# FMC_Main.net
KiCad netlist of a schematic drawn in Altium Designer
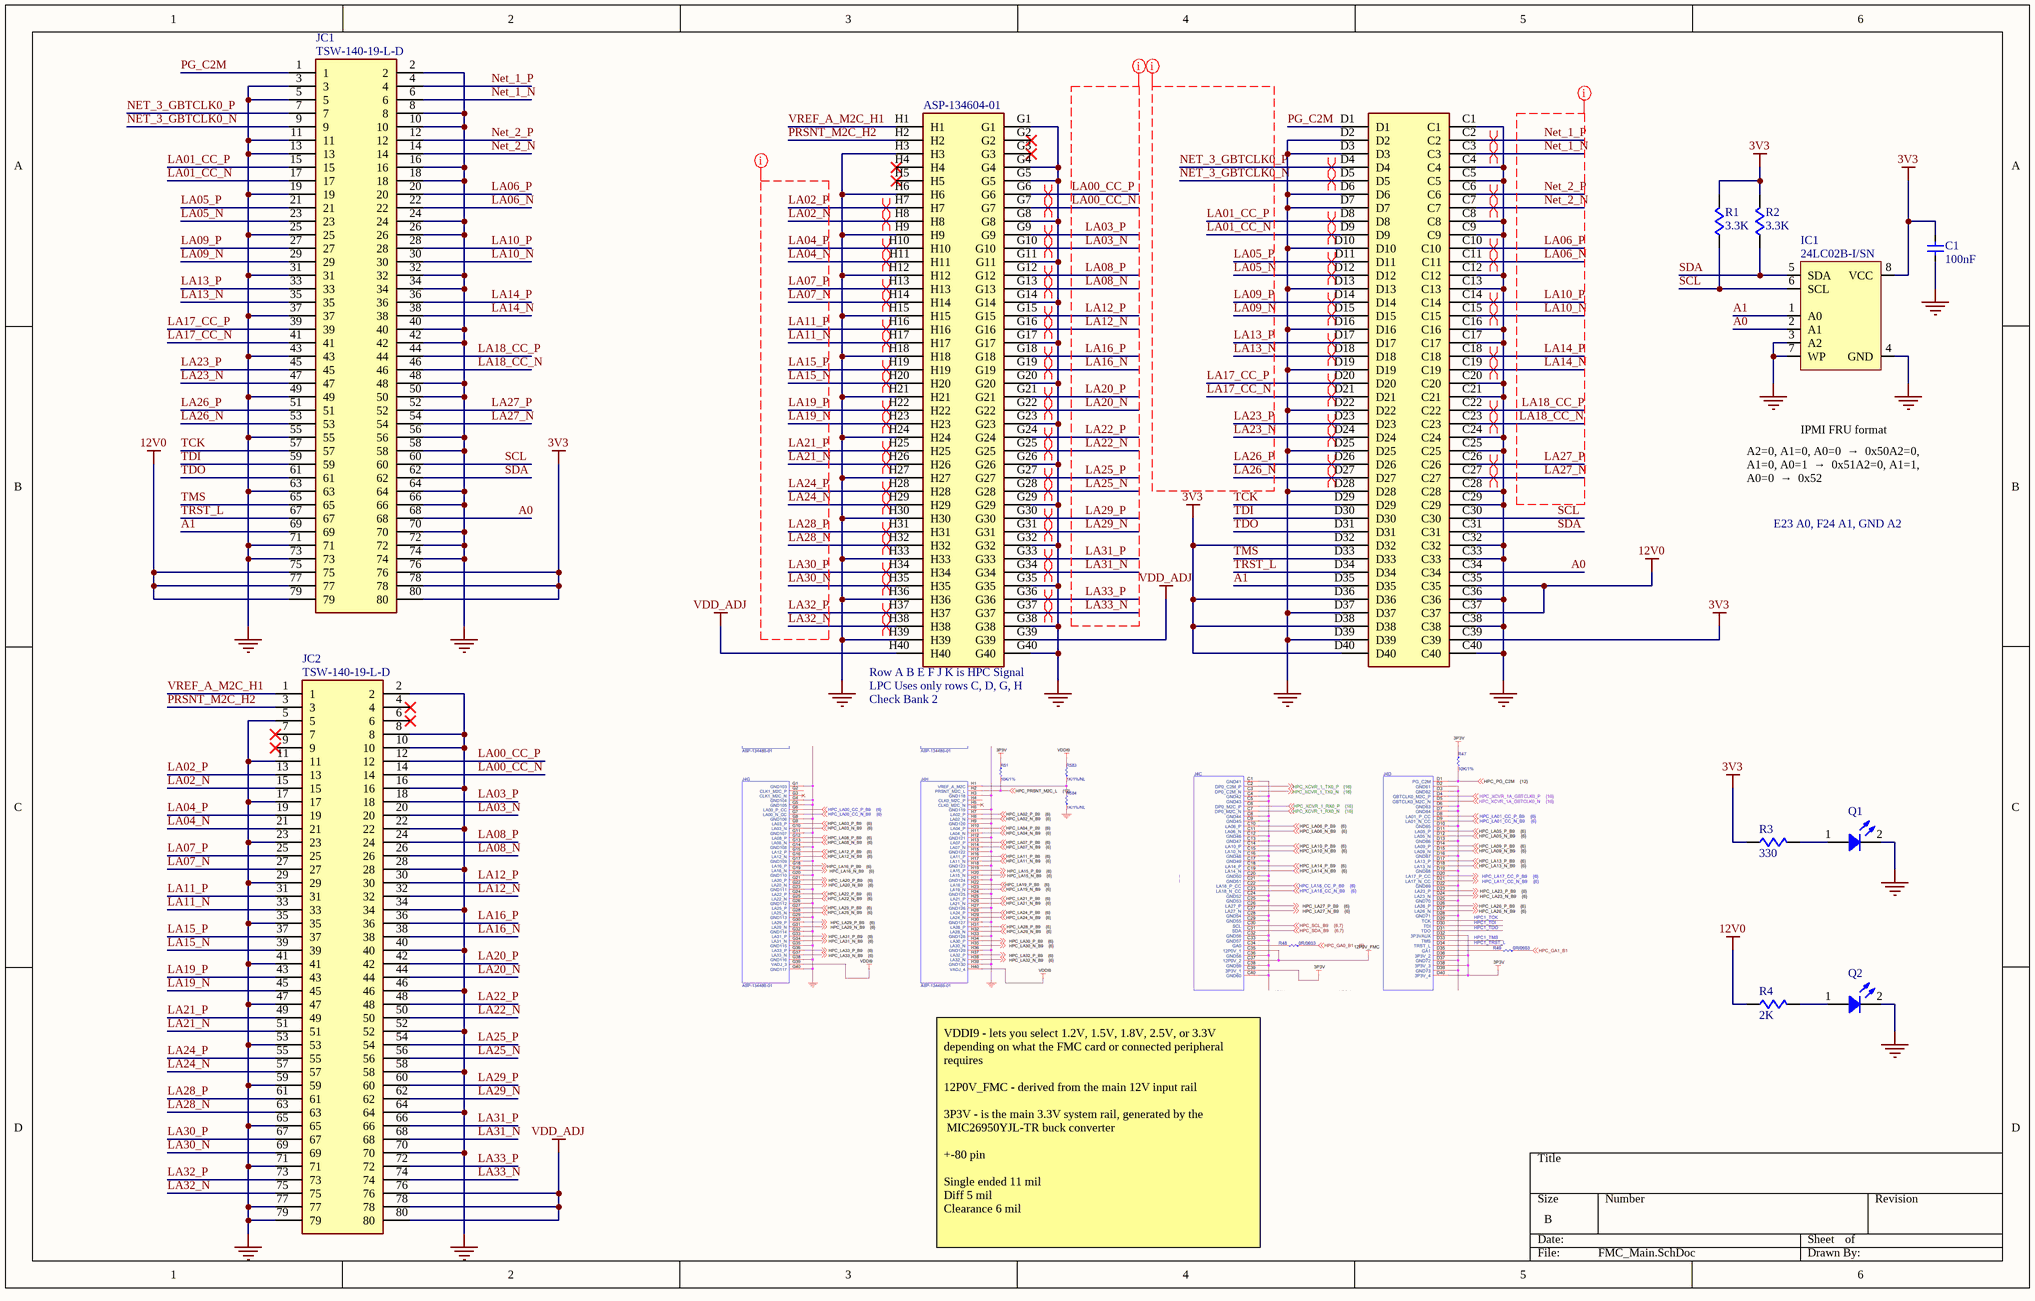
[diagram p0: FMC_Main.SchDoc]

(export (version "E")
  (design (tool "Eeschema 10.0.6"))
  (components
    (comp (ref "C1")
      (value "100nF")
      (footprint "CAP0402_N")
      (description "CAP CER 100nF 16V ±5% X7R 0402")
      (fields (field (name "TOLERANCE") "±5%") (field (name "VOLTAGE") "16V"))
      (libsource (lib "Database") (part "CAPCER"))
    )
    (comp (ref "IC1")
      (value "24LC02B-ISN")
      (footprint "SOIC_8")
      (description "IC EEPROM 2KBIT I2C 400KHZ 8MSOP")
      (fields (field (name "MANUFACTURER P/N 1") "24LC02B-I/SN"))
      (libsource (lib "Database") (part "24LC02B-ISN"))
    )
    (comp (ref "JC1")
      (value "TSW-140-19-L-D")
      (footprint "TSW-140-19-L-D")
      (description "CONN HEADER TH 80POS 2.54MM")
      (fields (field (name "MANUFACTURER P/N 1") "TSW-140-19-L-D"))
      (libsource (lib "Database") (part "TSW-140-19-L-D"))
    )
    (comp (ref "JC2")
      (value "TSW-140-19-L-D")
      (footprint "TSW-140-19-L-D")
      (description "CONN HEADER TH 80POS 2.54MM")
      (fields (field (name "MANUFACTURER P/N 1") "TSW-140-19-L-D"))
      (libsource (lib "Database") (part "TSW-140-19-L-D"))
    )
    (comp (ref "JC3")
      (value "ASP-134604-01")
      (footprint "ASP-134604-01")
      (description "CONN ARRAY PLUG 160POS SMD GOLD")
      (fields (field (name "MANUFACTURER P/N 1") "ASP-134604-01"))
      (libsource (lib "Database") (part "ASP-134604-01"))
    )
    (comp (ref "Q1")
      (value "LED")
      (footprint "0603LED")
      (description "LED YELLOW SMD 0603")
      (fields (field (name "VOLTAGE") "3V"))
      (libsource (lib "Database") (part "LED"))
    )
    (comp (ref "Q2")
      (value "LED")
      (footprint "0603LED")
      (description "LED YELLOW SMD 0603")
      (fields (field (name "VOLTAGE") "3V"))
      (libsource (lib "Database") (part "LED"))
    )
    (comp (ref "R1")
      (value "3.3K")
      (footprint "RES0402_N")
      (description "RES SMD 3.3K 1% 1/16W 0402")
      (fields (field (name "POWER") "1/16W") (field (name "TOLERANCE") "1%"))
      (libsource (lib "Database") (part "RES"))
    )
    (comp (ref "R2")
      (value "3.3K")
      (footprint "RES0402_N")
      (description "RES SMD 3.3K 1% 1/16W 0402")
      (fields (field (name "POWER") "1/16W") (field (name "TOLERANCE") "1%"))
      (libsource (lib "Database") (part "RES"))
    )
    (comp (ref "R3")
      (value "330")
      (footprint "RES0402_N")
      (description "RES 330 OHM 1% 1/10W 0402")
      (fields (field (name "POWER") "1/10W") (field (name "TOLERANCE") "1%"))
      (libsource (lib "Database") (part "RES"))
    )
    (comp (ref "R4")
      (value "2K")
      (footprint "RES0402_N")
      (description "RES SMD 2K 1% 1/16W 0402")
      (fields (field (name "POWER") "1/16W") (field (name "TOLERANCE") "1%"))
      (libsource (lib "Database") (part "RES"))
    )
  )
  (nets
    (net (code "1") (name "/A0") (class "Default")
      (node (ref "IC1") (pin "2") (pinfunction "A1_2") (pintype "power_in"))
      (node (ref "JC1") (pin "68") (pinfunction "68_68") (pintype "passive"))
      (node (ref "JC3") (pin "C34") (pinfunction "C34_C34") (pintype "passive"))
    )
    (net (code "2") (name "/A1") (class "Default")
      (node (ref "IC1") (pin "1") (pinfunction "A0_1") (pintype "power_in"))
      (node (ref "JC1") (pin "69") (pinfunction "69_69") (pintype "passive"))
      (node (ref "JC3") (pin "D35") (pinfunction "D35_D35") (pintype "passive"))
    )
    (net (code "3") (name "/LA00_CC_N") (class "Default")
      (node (ref "JC2") (pin "14") (pinfunction "14_14") (pintype "passive"))
      (node (ref "JC3") (pin "G7") (pinfunction "G7_G7") (pintype "passive"))
    )
    (net (code "4") (name "/LA00_CC_P") (class "Default")
      (node (ref "JC2") (pin "12") (pinfunction "12_12") (pintype "passive"))
      (node (ref "JC3") (pin "G6") (pinfunction "G6_G6") (pintype "passive"))
    )
    (net (code "5") (name "/LA01_CC_N") (class "Default")
      (node (ref "JC1") (pin "17") (pinfunction "17_17") (pintype "passive"))
      (node (ref "JC3") (pin "D9") (pinfunction "D9_D9") (pintype "passive"))
    )
    (net (code "6") (name "/LA01_CC_P") (class "Default")
      (node (ref "JC1") (pin "15") (pinfunction "15_15") (pintype "passive"))
      (node (ref "JC3") (pin "D8") (pinfunction "D8_D8") (pintype "passive"))
    )
    (net (code "7") (name "/LA02_N") (class "Default")
      (node (ref "JC2") (pin "15") (pinfunction "15_15") (pintype "passive"))
      (node (ref "JC3") (pin "H8") (pinfunction "H8_H8") (pintype "passive"))
    )
    (net (code "8") (name "/LA02_P") (class "Default")
      (node (ref "JC2") (pin "13") (pinfunction "13_13") (pintype "passive"))
      (node (ref "JC3") (pin "H7") (pinfunction "H7_H7") (pintype "passive"))
    )
    (net (code "9") (name "/LA03_N") (class "Default")
      (node (ref "JC2") (pin "20") (pinfunction "20_20") (pintype "passive"))
      (node (ref "JC3") (pin "G10") (pinfunction "G10_G10") (pintype "passive"))
    )
    (net (code "10") (name "/LA03_P") (class "Default")
      (node (ref "JC2") (pin "18") (pinfunction "18_18") (pintype "passive"))
      (node (ref "JC3") (pin "G9") (pinfunction "G9_G9") (pintype "passive"))
    )
    (net (code "11") (name "/LA04_N") (class "Default")
      (node (ref "JC2") (pin "21") (pinfunction "21_21") (pintype "passive"))
      (node (ref "JC3") (pin "H11") (pinfunction "H11_H11") (pintype "passive"))
    )
    (net (code "12") (name "/LA04_P") (class "Default")
      (node (ref "JC2") (pin "19") (pinfunction "19_19") (pintype "passive"))
      (node (ref "JC3") (pin "H10") (pinfunction "H10_H10") (pintype "passive"))
    )
    (net (code "13") (name "/LA05_N") (class "Default")
      (node (ref "JC1") (pin "23") (pinfunction "23_23") (pintype "passive"))
      (node (ref "JC3") (pin "D12") (pinfunction "D12_D12") (pintype "passive"))
    )
    (net (code "14") (name "/LA05_P") (class "Default")
      (node (ref "JC1") (pin "21") (pinfunction "21_21") (pintype "passive"))
      (node (ref "JC3") (pin "D11") (pinfunction "D11_D11") (pintype "passive"))
    )
    (net (code "15") (name "/LA06_N") (class "Default")
      (node (ref "JC1") (pin "22") (pinfunction "22_22") (pintype "passive"))
      (node (ref "JC3") (pin "C11") (pinfunction "C11_C11") (pintype "passive"))
    )
    (net (code "16") (name "/LA06_P") (class "Default")
      (node (ref "JC1") (pin "20") (pinfunction "20_20") (pintype "passive"))
      (node (ref "JC3") (pin "C10") (pinfunction "C10_C10") (pintype "passive"))
    )
    (net (code "17") (name "/LA07_N") (class "Default")
      (node (ref "JC2") (pin "27") (pinfunction "27_27") (pintype "passive"))
      (node (ref "JC3") (pin "H14") (pinfunction "H14_H14") (pintype "passive"))
    )
    (net (code "18") (name "/LA07_P") (class "Default")
      (node (ref "JC2") (pin "25") (pinfunction "25_25") (pintype "passive"))
      (node (ref "JC3") (pin "H13") (pinfunction "H13_H13") (pintype "passive"))
    )
    (net (code "19") (name "/LA08_N") (class "Default")
      (node (ref "JC2") (pin "26") (pinfunction "26_26") (pintype "passive"))
      (node (ref "JC3") (pin "G13") (pinfunction "G13_G13") (pintype "passive"))
    )
    (net (code "20") (name "/LA08_P") (class "Default")
      (node (ref "JC2") (pin "24") (pinfunction "24_24") (pintype "passive"))
      (node (ref "JC3") (pin "G12") (pinfunction "G12_G12") (pintype "passive"))
    )
    (net (code "21") (name "/LA09_N") (class "Default")
      (node (ref "JC1") (pin "29") (pinfunction "29_29") (pintype "passive"))
      (node (ref "JC3") (pin "D15") (pinfunction "D15_D15") (pintype "passive"))
    )
    (net (code "22") (name "/LA09_P") (class "Default")
      (node (ref "JC1") (pin "27") (pinfunction "27_27") (pintype "passive"))
      (node (ref "JC3") (pin "D14") (pinfunction "D14_D14") (pintype "passive"))
    )
    (net (code "23") (name "/LA10_N") (class "Default")
      (node (ref "JC1") (pin "30") (pinfunction "30_30") (pintype "passive"))
      (node (ref "JC3") (pin "C15") (pinfunction "C15_C15") (pintype "passive"))
    )
    (net (code "24") (name "/LA10_P") (class "Default")
      (node (ref "JC1") (pin "28") (pinfunction "28_28") (pintype "passive"))
      (node (ref "JC3") (pin "C14") (pinfunction "C14_C14") (pintype "passive"))
    )
    (net (code "25") (name "/LA11_N") (class "Default")
      (node (ref "JC2") (pin "33") (pinfunction "33_33") (pintype "passive"))
      (node (ref "JC3") (pin "H17") (pinfunction "H17_H17") (pintype "passive"))
    )
    (net (code "26") (name "/LA11_P") (class "Default")
      (node (ref "JC2") (pin "31") (pinfunction "31_31") (pintype "passive"))
      (node (ref "JC3") (pin "H16") (pinfunction "H16_H16") (pintype "passive"))
    )
    (net (code "27") (name "/LA12_N") (class "Default")
      (node (ref "JC2") (pin "32") (pinfunction "32_32") (pintype "passive"))
      (node (ref "JC3") (pin "G16") (pinfunction "G16_G16") (pintype "passive"))
    )
    (net (code "28") (name "/LA12_P") (class "Default")
      (node (ref "JC2") (pin "30") (pinfunction "30_30") (pintype "passive"))
      (node (ref "JC3") (pin "G15") (pinfunction "G15_G15") (pintype "passive"))
    )
    (net (code "29") (name "/LA13_N") (class "Default")
      (node (ref "JC1") (pin "35") (pinfunction "35_35") (pintype "passive"))
      (node (ref "JC3") (pin "D18") (pinfunction "D18_D18") (pintype "passive"))
    )
    (net (code "30") (name "/LA13_P") (class "Default")
      (node (ref "JC1") (pin "33") (pinfunction "33_33") (pintype "passive"))
      (node (ref "JC3") (pin "D17") (pinfunction "D17_D17") (pintype "passive"))
    )
    (net (code "31") (name "/LA14_N") (class "Default")
      (node (ref "JC1") (pin "38") (pinfunction "38_38") (pintype "passive"))
      (node (ref "JC3") (pin "C19") (pinfunction "C19_C19") (pintype "passive"))
    )
    (net (code "32") (name "/LA14_P") (class "Default")
      (node (ref "JC1") (pin "36") (pinfunction "36_36") (pintype "passive"))
      (node (ref "JC3") (pin "C18") (pinfunction "C18_C18") (pintype "passive"))
    )
    (net (code "33") (name "/LA15_N") (class "Default")
      (node (ref "JC2") (pin "39") (pinfunction "39_39") (pintype "passive"))
      (node (ref "JC3") (pin "H20") (pinfunction "H20_H20") (pintype "passive"))
    )
    (net (code "34") (name "/LA15_P") (class "Default")
      (node (ref "JC2") (pin "37") (pinfunction "37_37") (pintype "passive"))
      (node (ref "JC3") (pin "H19") (pinfunction "H19_H19") (pintype "passive"))
    )
    (net (code "35") (name "/LA16_N") (class "Default")
      (node (ref "JC2") (pin "38") (pinfunction "38_38") (pintype "passive"))
      (node (ref "JC3") (pin "G19") (pinfunction "G19_G19") (pintype "passive"))
    )
    (net (code "36") (name "/LA16_P") (class "Default")
      (node (ref "JC2") (pin "36") (pinfunction "36_36") (pintype "passive"))
      (node (ref "JC3") (pin "G18") (pinfunction "G18_G18") (pintype "passive"))
    )
    (net (code "37") (name "/LA17_CC_N") (class "Default")
      (node (ref "JC1") (pin "41") (pinfunction "41_41") (pintype "passive"))
      (node (ref "JC3") (pin "D21") (pinfunction "D21_D21") (pintype "passive"))
    )
    (net (code "38") (name "/LA17_CC_P") (class "Default")
      (node (ref "JC1") (pin "39") (pinfunction "39_39") (pintype "passive"))
      (node (ref "JC3") (pin "D20") (pinfunction "D20_D20") (pintype "passive"))
    )
    (net (code "39") (name "/LA18_CC_N") (class "Default")
      (node (ref "JC1") (pin "46") (pinfunction "46_46") (pintype "passive"))
      (node (ref "JC3") (pin "C23") (pinfunction "C23_C23") (pintype "passive"))
    )
    (net (code "40") (name "/LA18_CC_P") (class "Default")
      (node (ref "JC1") (pin "44") (pinfunction "44_44") (pintype "passive"))
      (node (ref "JC3") (pin "C22") (pinfunction "C22_C22") (pintype "passive"))
    )
    (net (code "41") (name "/LA19_N") (class "Default")
      (node (ref "JC2") (pin "45") (pinfunction "45_45") (pintype "passive"))
      (node (ref "JC3") (pin "H23") (pinfunction "H23_H23") (pintype "passive"))
    )
    (net (code "42") (name "/LA19_P") (class "Default")
      (node (ref "JC2") (pin "43") (pinfunction "43_43") (pintype "passive"))
      (node (ref "JC3") (pin "H22") (pinfunction "H22_H22") (pintype "passive"))
    )
    (net (code "43") (name "/LA20_N") (class "Default")
      (node (ref "JC2") (pin "44") (pinfunction "44_44") (pintype "passive"))
      (node (ref "JC3") (pin "G22") (pinfunction "G22_G22") (pintype "passive"))
    )
    (net (code "44") (name "/LA20_P") (class "Default")
      (node (ref "JC2") (pin "42") (pinfunction "42_42") (pintype "passive"))
      (node (ref "JC3") (pin "G21") (pinfunction "G21_G21") (pintype "passive"))
    )
    (net (code "45") (name "/LA21_N") (class "Default")
      (node (ref "JC2") (pin "51") (pinfunction "51_51") (pintype "passive"))
      (node (ref "JC3") (pin "H26") (pinfunction "H26_H26") (pintype "passive"))
    )
    (net (code "46") (name "/LA21_P") (class "Default")
      (node (ref "JC2") (pin "49") (pinfunction "49_49") (pintype "passive"))
      (node (ref "JC3") (pin "H25") (pinfunction "H25_H25") (pintype "passive"))
    )
    (net (code "47") (name "/LA22_N") (class "Default")
      (node (ref "JC2") (pin "50") (pinfunction "50_50") (pintype "passive"))
      (node (ref "JC3") (pin "G25") (pinfunction "G25_G25") (pintype "passive"))
    )
    (net (code "48") (name "/LA22_P") (class "Default")
      (node (ref "JC2") (pin "48") (pinfunction "48_48") (pintype "passive"))
      (node (ref "JC3") (pin "G24") (pinfunction "G24_G24") (pintype "passive"))
    )
    (net (code "49") (name "/LA23_N") (class "Default")
      (node (ref "JC1") (pin "47") (pinfunction "47_47") (pintype "passive"))
      (node (ref "JC3") (pin "D24") (pinfunction "D24_D24") (pintype "passive"))
    )
    (net (code "50") (name "/LA23_P") (class "Default")
      (node (ref "JC1") (pin "45") (pinfunction "45_45") (pintype "passive"))
      (node (ref "JC3") (pin "D23") (pinfunction "D23_D23") (pintype "passive"))
    )
    (net (code "51") (name "/LA24_N") (class "Default")
      (node (ref "JC2") (pin "57") (pinfunction "57_57") (pintype "passive"))
      (node (ref "JC3") (pin "H29") (pinfunction "H29_H29") (pintype "passive"))
    )
    (net (code "52") (name "/LA24_P") (class "Default")
      (node (ref "JC2") (pin "55") (pinfunction "55_55") (pintype "passive"))
      (node (ref "JC3") (pin "H28") (pinfunction "H28_H28") (pintype "passive"))
    )
    (net (code "53") (name "/LA25_N") (class "Default")
      (node (ref "JC2") (pin "56") (pinfunction "56_56") (pintype "passive"))
      (node (ref "JC3") (pin "G28") (pinfunction "G28_G28") (pintype "passive"))
    )
    (net (code "54") (name "/LA25_P") (class "Default")
      (node (ref "JC2") (pin "54") (pinfunction "54_54") (pintype "passive"))
      (node (ref "JC3") (pin "G27") (pinfunction "G27_G27") (pintype "passive"))
    )
    (net (code "55") (name "/LA26_N") (class "Default")
      (node (ref "JC1") (pin "53") (pinfunction "53_53") (pintype "passive"))
      (node (ref "JC3") (pin "D27") (pinfunction "D27_D27") (pintype "passive"))
    )
    (net (code "56") (name "/LA26_P") (class "Default")
      (node (ref "JC1") (pin "51") (pinfunction "51_51") (pintype "passive"))
      (node (ref "JC3") (pin "D26") (pinfunction "D26_D26") (pintype "passive"))
    )
    (net (code "57") (name "/LA27_N") (class "Default")
      (node (ref "JC1") (pin "54") (pinfunction "54_54") (pintype "passive"))
      (node (ref "JC3") (pin "C27") (pinfunction "C27_C27") (pintype "passive"))
    )
    (net (code "58") (name "/LA27_P") (class "Default")
      (node (ref "JC1") (pin "52") (pinfunction "52_52") (pintype "passive"))
      (node (ref "JC3") (pin "C26") (pinfunction "C26_C26") (pintype "passive"))
    )
    (net (code "59") (name "/LA28_N") (class "Default")
      (node (ref "JC2") (pin "63") (pinfunction "63_63") (pintype "passive"))
      (node (ref "JC3") (pin "H32") (pinfunction "H32_H32") (pintype "passive"))
    )
    (net (code "60") (name "/LA28_P") (class "Default")
      (node (ref "JC2") (pin "61") (pinfunction "61_61") (pintype "passive"))
      (node (ref "JC3") (pin "H31") (pinfunction "H31_H31") (pintype "passive"))
    )
    (net (code "61") (name "/LA29_N") (class "Default")
      (node (ref "JC2") (pin "62") (pinfunction "62_62") (pintype "passive"))
      (node (ref "JC3") (pin "G31") (pinfunction "G31_G31") (pintype "passive"))
    )
    (net (code "62") (name "/LA29_P") (class "Default")
      (node (ref "JC2") (pin "60") (pinfunction "60_60") (pintype "passive"))
      (node (ref "JC3") (pin "G30") (pinfunction "G30_G30") (pintype "passive"))
    )
    (net (code "63") (name "/LA30_N") (class "Default")
      (node (ref "JC2") (pin "69") (pinfunction "69_69") (pintype "passive"))
      (node (ref "JC3") (pin "H35") (pinfunction "H35_H35") (pintype "passive"))
    )
    (net (code "64") (name "/LA30_P") (class "Default")
      (node (ref "JC2") (pin "67") (pinfunction "67_67") (pintype "passive"))
      (node (ref "JC3") (pin "H34") (pinfunction "H34_H34") (pintype "passive"))
    )
    (net (code "65") (name "/LA31_N") (class "Default")
      (node (ref "JC2") (pin "68") (pinfunction "68_68") (pintype "passive"))
      (node (ref "JC3") (pin "G34") (pinfunction "G34_G34") (pintype "passive"))
    )
    (net (code "66") (name "/LA31_P") (class "Default")
      (node (ref "JC2") (pin "66") (pinfunction "66_66") (pintype "passive"))
      (node (ref "JC3") (pin "G33") (pinfunction "G33_G33") (pintype "passive"))
    )
    (net (code "67") (name "/LA32_N") (class "Default")
      (node (ref "JC2") (pin "75") (pinfunction "75_75") (pintype "passive"))
      (node (ref "JC3") (pin "H38") (pinfunction "H38_H38") (pintype "passive"))
    )
    (net (code "68") (name "/LA32_P") (class "Default")
      (node (ref "JC2") (pin "73") (pinfunction "73_73") (pintype "passive"))
      (node (ref "JC3") (pin "H37") (pinfunction "H37_H37") (pintype "passive"))
    )
    (net (code "69") (name "/LA33_N") (class "Default")
      (node (ref "JC2") (pin "74") (pinfunction "74_74") (pintype "passive"))
      (node (ref "JC3") (pin "G37") (pinfunction "G37_G37") (pintype "passive"))
    )
    (net (code "70") (name "/LA33_P") (class "Default")
      (node (ref "JC2") (pin "72") (pinfunction "72_72") (pintype "passive"))
      (node (ref "JC3") (pin "G36") (pinfunction "G36_G36") (pintype "passive"))
    )
    (net (code "71") (name "/NET_3_GBTCLK0_N") (class "Default")
      (node (ref "JC1") (pin "9") (pinfunction "9_9") (pintype "passive"))
      (node (ref "JC3") (pin "D5") (pinfunction "D5_D5") (pintype "passive"))
    )
    (net (code "72") (name "/NET_3_GBTCLK0_P") (class "Default")
      (node (ref "JC1") (pin "7") (pinfunction "7_7") (pintype "passive"))
      (node (ref "JC3") (pin "D4") (pinfunction "D4_D4") (pintype "passive"))
    )
    (net (code "73") (name "/Net_1_N") (class "Default")
      (node (ref "JC1") (pin "6") (pinfunction "6_6") (pintype "passive"))
      (node (ref "JC3") (pin "C3") (pinfunction "C3_C3") (pintype "passive"))
    )
    (net (code "74") (name "/Net_1_P") (class "Default")
      (node (ref "JC1") (pin "4") (pinfunction "4_4") (pintype "passive"))
      (node (ref "JC3") (pin "C2") (pinfunction "C2_C2") (pintype "passive"))
    )
    (net (code "75") (name "/Net_2_N") (class "Default")
      (node (ref "JC1") (pin "14") (pinfunction "14_14") (pintype "passive"))
      (node (ref "JC3") (pin "C7") (pinfunction "C7_C7") (pintype "passive"))
    )
    (net (code "76") (name "/Net_2_P") (class "Default")
      (node (ref "JC1") (pin "12") (pinfunction "12_12") (pintype "passive"))
      (node (ref "JC3") (pin "C6") (pinfunction "C6_C6") (pintype "passive"))
    )
    (net (code "77") (name "/PG_C2M") (class "Default")
      (node (ref "JC1") (pin "1") (pinfunction "1_1") (pintype "passive"))
      (node (ref "JC3") (pin "D1") (pinfunction "D1_D1") (pintype "passive"))
    )
    (net (code "78") (name "/PRSNT_M2C_H2") (class "Default")
      (node (ref "JC2") (pin "3") (pinfunction "3_3") (pintype "passive"))
      (node (ref "JC3") (pin "H2") (pinfunction "H2_H2") (pintype "passive"))
    )
    (net (code "79") (name "/SCL") (class "Default")
      (node (ref "IC1") (pin "6") (pinfunction "SCL_6") (pintype "power_in"))
      (node (ref "JC1") (pin "60") (pinfunction "60_60") (pintype "passive"))
      (node (ref "JC3") (pin "C30") (pinfunction "C30_C30") (pintype "passive"))
      (node (ref "R1") (pin "1") (pinfunction "1_1") (pintype "passive"))
    )
    (net (code "80") (name "/SDA") (class "Default")
      (node (ref "IC1") (pin "5") (pinfunction "SDA_5") (pintype "power_in"))
      (node (ref "JC1") (pin "62") (pinfunction "62_62") (pintype "passive"))
      (node (ref "JC3") (pin "C31") (pinfunction "C31_C31") (pintype "passive"))
      (node (ref "R2") (pin "1") (pinfunction "1_1") (pintype "passive"))
    )
    (net (code "81") (name "/TCK") (class "Default")
      (node (ref "JC1") (pin "57") (pinfunction "57_57") (pintype "passive"))
      (node (ref "JC3") (pin "D29") (pinfunction "D29_D29") (pintype "passive"))
    )
    (net (code "82") (name "/TDI") (class "Default")
      (node (ref "JC1") (pin "59") (pinfunction "59_59") (pintype "passive"))
      (node (ref "JC3") (pin "D30") (pinfunction "D30_D30") (pintype "passive"))
    )
    (net (code "83") (name "/TDO") (class "Default")
      (node (ref "JC1") (pin "61") (pinfunction "61_61") (pintype "passive"))
      (node (ref "JC3") (pin "D31") (pinfunction "D31_D31") (pintype "passive"))
    )
    (net (code "84") (name "/TMS") (class "Default")
      (node (ref "JC1") (pin "65") (pinfunction "65_65") (pintype "passive"))
      (node (ref "JC3") (pin "D33") (pinfunction "D33_D33") (pintype "passive"))
    )
    (net (code "85") (name "/TRST_L") (class "Default")
      (node (ref "JC1") (pin "67") (pinfunction "67_67") (pintype "passive"))
      (node (ref "JC3") (pin "D34") (pinfunction "D34_D34") (pintype "passive"))
    )
    (net (code "86") (name "/VREF_A_M2C_H1") (class "Default")
      (node (ref "JC2") (pin "1") (pinfunction "1_1") (pintype "passive"))
      (node (ref "JC3") (pin "H1") (pinfunction "H1_H1") (pintype "passive"))
    )
    (net (code "87") (name "3V3") (class "Default")
      (node (ref "C1") (pin "2") (pinfunction "2_2") (pintype "passive"))
      (node (ref "IC1") (pin "8") (pinfunction "VCC_8") (pintype "power_in"))
      (node (ref "JC1") (pin "76") (pinfunction "76_76") (pintype "passive"))
      (node (ref "JC1") (pin "78") (pinfunction "78_78") (pintype "passive"))
      (node (ref "JC1") (pin "80") (pinfunction "80_80") (pintype "passive"))
      (node (ref "JC3") (pin "C39") (pinfunction "C39_C39") (pintype "passive"))
      (node (ref "JC3") (pin "D32") (pinfunction "D32_D32") (pintype "passive"))
      (node (ref "JC3") (pin "D36") (pinfunction "D36_D36") (pintype "passive"))
      (node (ref "JC3") (pin "D38") (pinfunction "D38_D38") (pintype "passive"))
      (node (ref "JC3") (pin "D40") (pinfunction "D40_D40") (pintype "passive"))
      (node (ref "R1") (pin "2") (pinfunction "2_2") (pintype "passive"))
      (node (ref "R2") (pin "2") (pinfunction "2_2") (pintype "passive"))
      (node (ref "R3") (pin "1") (pinfunction "1_1") (pintype "passive"))
    )
    (net (code "88") (name "12V0") (class "Default")
      (node (ref "JC1") (pin "75") (pinfunction "75_75") (pintype "passive"))
      (node (ref "JC1") (pin "77") (pinfunction "77_77") (pintype "passive"))
      (node (ref "JC1") (pin "79") (pinfunction "79_79") (pintype "passive"))
      (node (ref "JC3") (pin "C35") (pinfunction "C35_C35") (pintype "passive"))
      (node (ref "JC3") (pin "C37") (pinfunction "C37_C37") (pintype "passive"))
      (node (ref "R4") (pin "1") (pinfunction "1_1") (pintype "passive"))
    )
    (net (code "89") (name "GND") (class "Default")
      (node (ref "C1") (pin "1") (pinfunction "1_1") (pintype "passive"))
      (node (ref "IC1") (pin "3") (pinfunction "A2_3") (pintype "power_in"))
      (node (ref "IC1") (pin "4") (pinfunction "GND_4") (pintype "power_in"))
      (node (ref "IC1") (pin "7") (pinfunction "WP_7") (pintype "power_in"))
      (node (ref "JC1") (pin "10") (pinfunction "10_10") (pintype "passive"))
      (node (ref "JC1") (pin "11") (pinfunction "11_11") (pintype "passive"))
      (node (ref "JC1") (pin "13") (pinfunction "13_13") (pintype "passive"))
      (node (ref "JC1") (pin "16") (pinfunction "16_16") (pintype "passive"))
      (node (ref "JC1") (pin "18") (pinfunction "18_18") (pintype "passive"))
      (node (ref "JC1") (pin "19") (pinfunction "19_19") (pintype "passive"))
      (node (ref "JC1") (pin "2") (pinfunction "2_2") (pintype "passive"))
      (node (ref "JC1") (pin "24") (pinfunction "24_24") (pintype "passive"))
      (node (ref "JC1") (pin "25") (pinfunction "25_25") (pintype "passive"))
      (node (ref "JC1") (pin "26") (pinfunction "26_26") (pintype "passive"))
      (node (ref "JC1") (pin "3") (pinfunction "3_3") (pintype "passive"))
      (node (ref "JC1") (pin "31") (pinfunction "31_31") (pintype "passive"))
      (node (ref "JC1") (pin "32") (pinfunction "32_32") (pintype "passive"))
      (node (ref "JC1") (pin "34") (pinfunction "34_34") (pintype "passive"))
      (node (ref "JC1") (pin "37") (pinfunction "37_37") (pintype "passive"))
      (node (ref "JC1") (pin "40") (pinfunction "40_40") (pintype "passive"))
      (node (ref "JC1") (pin "42") (pinfunction "42_42") (pintype "passive"))
      (node (ref "JC1") (pin "43") (pinfunction "43_43") (pintype "passive"))
      (node (ref "JC1") (pin "48") (pinfunction "48_48") (pintype "passive"))
      (node (ref "JC1") (pin "49") (pinfunction "49_49") (pintype "passive"))
      (node (ref "JC1") (pin "5") (pinfunction "5_5") (pintype "passive"))
      (node (ref "JC1") (pin "50") (pinfunction "50_50") (pintype "passive"))
      (node (ref "JC1") (pin "55") (pinfunction "55_55") (pintype "passive"))
      (node (ref "JC1") (pin "56") (pinfunction "56_56") (pintype "passive"))
      (node (ref "JC1") (pin "58") (pinfunction "58_58") (pintype "passive"))
      (node (ref "JC1") (pin "63") (pinfunction "63_63") (pintype "passive"))
      (node (ref "JC1") (pin "64") (pinfunction "64_64") (pintype "passive"))
      (node (ref "JC1") (pin "66") (pinfunction "66_66") (pintype "passive"))
      (node (ref "JC1") (pin "70") (pinfunction "70_70") (pintype "passive"))
      (node (ref "JC1") (pin "71") (pinfunction "71_71") (pintype "passive"))
      (node (ref "JC1") (pin "72") (pinfunction "72_72") (pintype "passive"))
      (node (ref "JC1") (pin "73") (pinfunction "73_73") (pintype "passive"))
      (node (ref "JC1") (pin "74") (pinfunction "74_74") (pintype "passive"))
      (node (ref "JC1") (pin "8") (pinfunction "8_8") (pintype "passive"))
      (node (ref "JC2") (pin "10") (pinfunction "10_10") (pintype "passive"))
      (node (ref "JC2") (pin "11") (pinfunction "11_11") (pintype "passive"))
      (node (ref "JC2") (pin "16") (pinfunction "16_16") (pintype "passive"))
      (node (ref "JC2") (pin "17") (pinfunction "17_17") (pintype "passive"))
      (node (ref "JC2") (pin "2") (pinfunction "2_2") (pintype "passive"))
      (node (ref "JC2") (pin "22") (pinfunction "22_22") (pintype "passive"))
      (node (ref "JC2") (pin "23") (pinfunction "23_23") (pintype "passive"))
      (node (ref "JC2") (pin "28") (pinfunction "28_28") (pintype "passive"))
      (node (ref "JC2") (pin "29") (pinfunction "29_29") (pintype "passive"))
      (node (ref "JC2") (pin "34") (pinfunction "34_34") (pintype "passive"))
      (node (ref "JC2") (pin "35") (pinfunction "35_35") (pintype "passive"))
      (node (ref "JC2") (pin "40") (pinfunction "40_40") (pintype "passive"))
      (node (ref "JC2") (pin "41") (pinfunction "41_41") (pintype "passive"))
      (node (ref "JC2") (pin "46") (pinfunction "46_46") (pintype "passive"))
      (node (ref "JC2") (pin "47") (pinfunction "47_47") (pintype "passive"))
      (node (ref "JC2") (pin "5") (pinfunction "5_5") (pintype "passive"))
      (node (ref "JC2") (pin "52") (pinfunction "52_52") (pintype "passive"))
      (node (ref "JC2") (pin "53") (pinfunction "53_53") (pintype "passive"))
      (node (ref "JC2") (pin "58") (pinfunction "58_58") (pintype "passive"))
      (node (ref "JC2") (pin "59") (pinfunction "59_59") (pintype "passive"))
      (node (ref "JC2") (pin "64") (pinfunction "64_64") (pintype "passive"))
      (node (ref "JC2") (pin "65") (pinfunction "65_65") (pintype "passive"))
      (node (ref "JC2") (pin "70") (pinfunction "70_70") (pintype "passive"))
      (node (ref "JC2") (pin "71") (pinfunction "71_71") (pintype "passive"))
      (node (ref "JC2") (pin "77") (pinfunction "77_77") (pintype "passive"))
      (node (ref "JC2") (pin "79") (pinfunction "79_79") (pintype "passive"))
      (node (ref "JC2") (pin "8") (pinfunction "8_8") (pintype "passive"))
      (node (ref "JC3") (pin "C1") (pinfunction "C1_C1") (pintype "passive"))
      (node (ref "JC3") (pin "C12") (pinfunction "C12_C12") (pintype "passive"))
      (node (ref "JC3") (pin "C13") (pinfunction "C13_C13") (pintype "passive"))
      (node (ref "JC3") (pin "C16") (pinfunction "C16_C16") (pintype "passive"))
      (node (ref "JC3") (pin "C17") (pinfunction "C17_C17") (pintype "passive"))
      (node (ref "JC3") (pin "C20") (pinfunction "C20_C20") (pintype "passive"))
      (node (ref "JC3") (pin "C21") (pinfunction "C21_C21") (pintype "passive"))
      (node (ref "JC3") (pin "C24") (pinfunction "C24_C24") (pintype "passive"))
      (node (ref "JC3") (pin "C25") (pinfunction "C25_C25") (pintype "passive"))
      (node (ref "JC3") (pin "C28") (pinfunction "C28_C28") (pintype "passive"))
      (node (ref "JC3") (pin "C29") (pinfunction "C29_C29") (pintype "passive"))
      (node (ref "JC3") (pin "C32") (pinfunction "C32_C32") (pintype "passive"))
      (node (ref "JC3") (pin "C33") (pinfunction "C33_C33") (pintype "passive"))
      (node (ref "JC3") (pin "C36") (pinfunction "C36_C36") (pintype "passive"))
      (node (ref "JC3") (pin "C38") (pinfunction "C38_C38") (pintype "passive"))
      (node (ref "JC3") (pin "C4") (pinfunction "C4_C4") (pintype "passive"))
      (node (ref "JC3") (pin "C40") (pinfunction "C40_C40") (pintype "passive"))
      (node (ref "JC3") (pin "C5") (pinfunction "C5_C5") (pintype "passive"))
      (node (ref "JC3") (pin "C8") (pinfunction "C8_C8") (pintype "passive"))
      (node (ref "JC3") (pin "C9") (pinfunction "C9_C9") (pintype "passive"))
      (node (ref "JC3") (pin "D10") (pinfunction "D10_D10") (pintype "passive"))
      (node (ref "JC3") (pin "D13") (pinfunction "D13_D13") (pintype "passive"))
      (node (ref "JC3") (pin "D16") (pinfunction "D16_D16") (pintype "passive"))
      (node (ref "JC3") (pin "D19") (pinfunction "D19_D19") (pintype "passive"))
      (node (ref "JC3") (pin "D2") (pinfunction "D2_D2") (pintype "passive"))
      (node (ref "JC3") (pin "D22") (pinfunction "D22_D22") (pintype "passive"))
      (node (ref "JC3") (pin "D25") (pinfunction "D25_D25") (pintype "passive"))
      (node (ref "JC3") (pin "D28") (pinfunction "D28_D28") (pintype "passive"))
      (node (ref "JC3") (pin "D3") (pinfunction "D3_D3") (pintype "passive"))
      (node (ref "JC3") (pin "D37") (pinfunction "D37_D37") (pintype "passive"))
      (node (ref "JC3") (pin "D39") (pinfunction "D39_D39") (pintype "passive"))
      (node (ref "JC3") (pin "D6") (pinfunction "D6_D6") (pintype "passive"))
      (node (ref "JC3") (pin "D7") (pinfunction "D7_D7") (pintype "passive"))
      (node (ref "JC3") (pin "G1") (pinfunction "G1_G1") (pintype "passive"))
      (node (ref "JC3") (pin "G11") (pinfunction "G11_G11") (pintype "passive"))
      (node (ref "JC3") (pin "G14") (pinfunction "G14_G14") (pintype "passive"))
      (node (ref "JC3") (pin "G17") (pinfunction "G17_G17") (pintype "passive"))
      (node (ref "JC3") (pin "G20") (pinfunction "G20_G20") (pintype "passive"))
      (node (ref "JC3") (pin "G23") (pinfunction "G23_G23") (pintype "passive"))
      (node (ref "JC3") (pin "G26") (pinfunction "G26_G26") (pintype "passive"))
      (node (ref "JC3") (pin "G29") (pinfunction "G29_G29") (pintype "passive"))
      (node (ref "JC3") (pin "G32") (pinfunction "G32_G32") (pintype "passive"))
      (node (ref "JC3") (pin "G35") (pinfunction "G35_G35") (pintype "passive"))
      (node (ref "JC3") (pin "G38") (pinfunction "G38_G38") (pintype "passive"))
      (node (ref "JC3") (pin "G4") (pinfunction "G4_G4") (pintype "passive"))
      (node (ref "JC3") (pin "G40") (pinfunction "G40_G40") (pintype "passive"))
      (node (ref "JC3") (pin "G5") (pinfunction "G5_G5") (pintype "passive"))
      (node (ref "JC3") (pin "G8") (pinfunction "G8_G8") (pintype "passive"))
      (node (ref "JC3") (pin "H12") (pinfunction "H12_H12") (pintype "passive"))
      (node (ref "JC3") (pin "H15") (pinfunction "H15_H15") (pintype "passive"))
      (node (ref "JC3") (pin "H18") (pinfunction "H18_H18") (pintype "passive"))
      (node (ref "JC3") (pin "H21") (pinfunction "H21_H21") (pintype "passive"))
      (node (ref "JC3") (pin "H24") (pinfunction "H24_H24") (pintype "passive"))
      (node (ref "JC3") (pin "H27") (pinfunction "H27_H27") (pintype "passive"))
      (node (ref "JC3") (pin "H3") (pinfunction "H3_H3") (pintype "passive"))
      (node (ref "JC3") (pin "H30") (pinfunction "H30_H30") (pintype "passive"))
      (node (ref "JC3") (pin "H33") (pinfunction "H33_H33") (pintype "passive"))
      (node (ref "JC3") (pin "H36") (pinfunction "H36_H36") (pintype "passive"))
      (node (ref "JC3") (pin "H39") (pinfunction "H39_H39") (pintype "passive"))
      (node (ref "JC3") (pin "H6") (pinfunction "H6_H6") (pintype "passive"))
      (node (ref "JC3") (pin "H9") (pinfunction "H9_H9") (pintype "passive"))
      (node (ref "Q1") (pin "2") (pinfunction "2_2") (pintype "passive"))
      (node (ref "Q2") (pin "2") (pinfunction "2_2") (pintype "passive"))
    )
    (net (code "90") (name "Net-(Q1-Pad1)") (class "Default")
      (node (ref "Q1") (pin "1") (pinfunction "1_1") (pintype "passive"))
      (node (ref "R3") (pin "2") (pinfunction "2_2") (pintype "passive"))
    )
    (net (code "91") (name "Net-(Q2-Pad1)") (class "Default")
      (node (ref "Q2") (pin "1") (pinfunction "1_1") (pintype "passive"))
      (node (ref "R4") (pin "2") (pinfunction "2_2") (pintype "passive"))
    )
    (net (code "92") (name "VDD_ADJ") (class "Default")
      (node (ref "JC2") (pin "76") (pinfunction "76_76") (pintype "passive"))
      (node (ref "JC2") (pin "78") (pinfunction "78_78") (pintype "passive"))
      (node (ref "JC2") (pin "80") (pinfunction "80_80") (pintype "passive"))
      (node (ref "JC3") (pin "G39") (pinfunction "G39_G39") (pintype "passive"))
      (node (ref "JC3") (pin "H40") (pinfunction "H40_H40") (pintype "passive"))
    )
    (net (code "93") (name "unconnected-(JC2-Pad4)") (class "Default")
      (node (ref "JC2") (pin "4") (pinfunction "4_4") (pintype "passive+no_connect"))
    )
    (net (code "94") (name "unconnected-(JC2-Pad6)") (class "Default")
      (node (ref "JC2") (pin "6") (pinfunction "6_6") (pintype "passive+no_connect"))
    )
    (net (code "95") (name "unconnected-(JC2-Pad7)") (class "Default")
      (node (ref "JC2") (pin "7") (pinfunction "7_7") (pintype "passive+no_connect"))
    )
    (net (code "96") (name "unconnected-(JC2-Pad9)") (class "Default")
      (node (ref "JC2") (pin "9") (pinfunction "9_9") (pintype "passive+no_connect"))
    )
    (net (code "97") (name "unconnected-(JC3-PadG2)") (class "Default")
      (node (ref "JC3") (pin "G2") (pinfunction "G2_G2") (pintype "passive+no_connect"))
    )
    (net (code "98") (name "unconnected-(JC3-PadG3)") (class "Default")
      (node (ref "JC3") (pin "G3") (pinfunction "G3_G3") (pintype "passive+no_connect"))
    )
    (net (code "99") (name "unconnected-(JC3-PadH4)") (class "Default")
      (node (ref "JC3") (pin "H4") (pinfunction "H4_H4") (pintype "passive+no_connect"))
    )
    (net (code "100") (name "unconnected-(JC3-PadH5)") (class "Default")
      (node (ref "JC3") (pin "H5") (pinfunction "H5_H5") (pintype "passive+no_connect"))
    )
  )
)
